# G431.net
KiCad netlist of a schematic drawn in Altium Designer
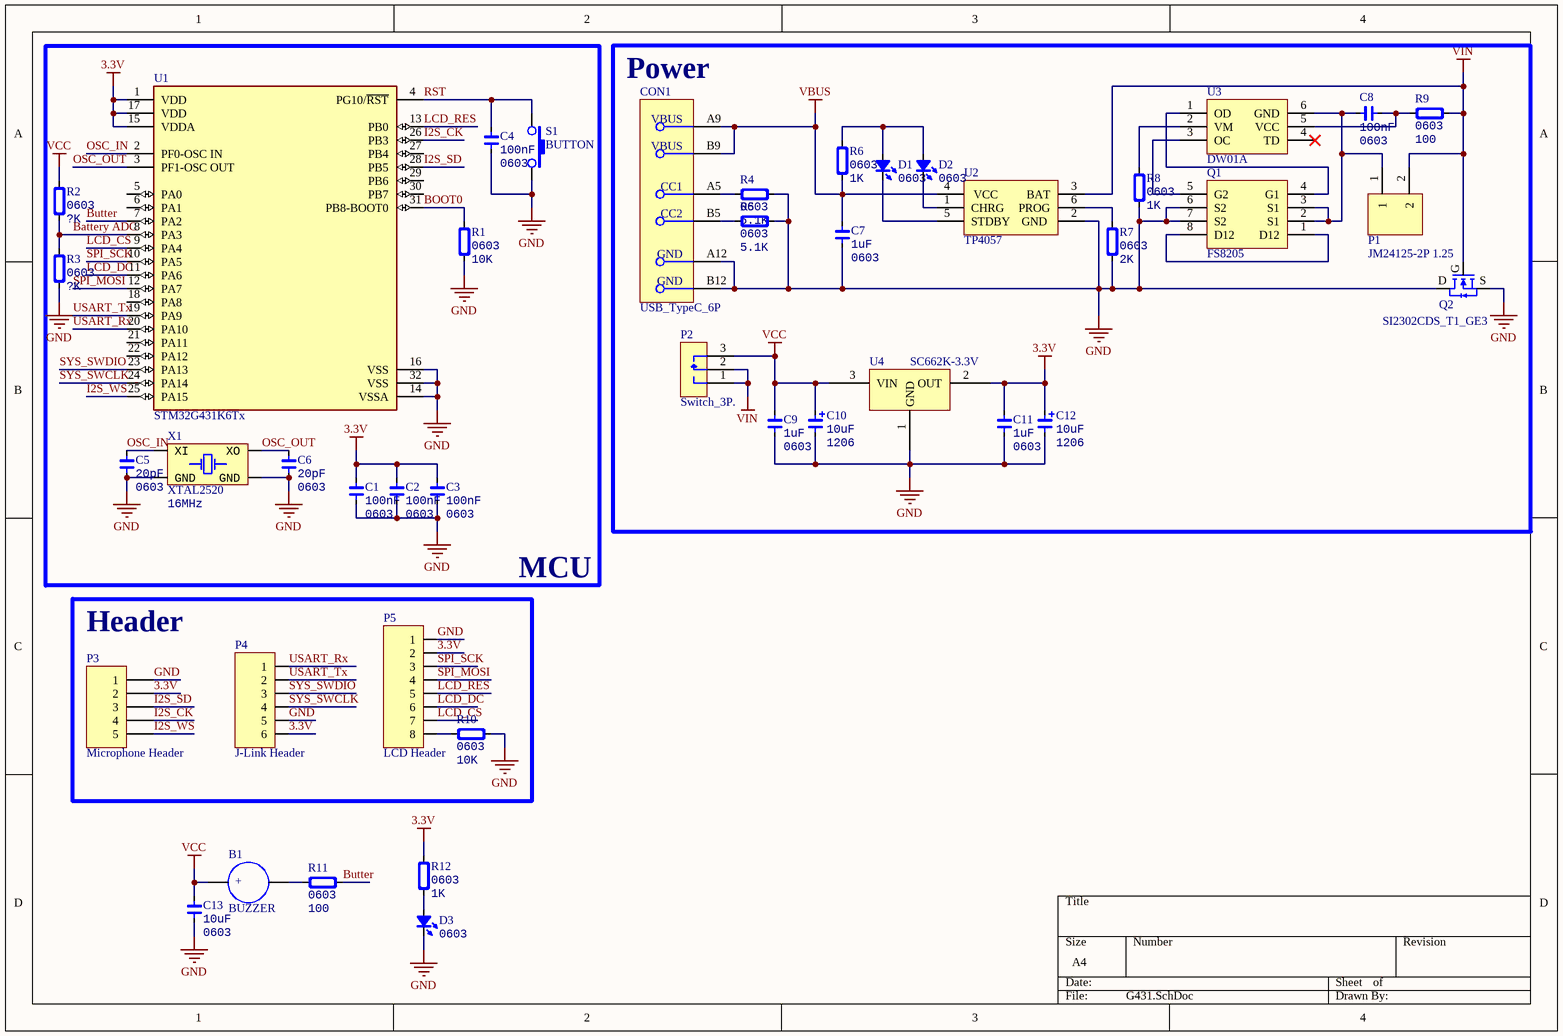
[diagram p0: G431.SchDoc]

(export (version "E")
  (design (tool "Eeschema 10.0.6"))
  (components
    (comp (ref "B1") (value "BUZZER") (footprint "BUZZER - 5020") (libsource (lib "Library") (part "BUZZER")))
    (comp (ref "C1")
      (value "100nF")
      (footprint "CAP_0603")
      (description "Capacitor")
      (fields (field (name "TYPE") "0603") (field (name "Comment") "C0603"))
      (libsource (lib "Library") (part "Cap_0603"))
    )
    (comp (ref "C2")
      (value "100nF")
      (footprint "CAP_0603")
      (description "Capacitor")
      (fields (field (name "TYPE") "0603") (field (name "Comment") "C0603"))
      (libsource (lib "Library") (part "Cap_0603"))
    )
    (comp (ref "C3")
      (value "100nF")
      (footprint "CAP_0603")
      (description "Capacitor")
      (fields (field (name "TYPE") "0603") (field (name "Comment") "C0603"))
      (libsource (lib "Library") (part "Cap_0603"))
    )
    (comp (ref "C4")
      (value "100nF")
      (footprint "CAP_0603")
      (description "Capacitor")
      (fields (field (name "TYPE") "0603") (field (name "Comment") "C0603"))
      (libsource (lib "") (part "Cap_0603_1"))
    )
    (comp (ref "C5")
      (value "20pF")
      (footprint "CAP_0603")
      (description "Capacitor")
      (fields (field (name "TYPE") "0603") (field (name "Comment") "C0603"))
      (libsource (lib "Library") (part "Cap_0603"))
    )
    (comp (ref "C6")
      (value "20pF")
      (footprint "CAP_0603")
      (description "Capacitor")
      (fields (field (name "TYPE") "0603") (field (name "Comment") "C0603"))
      (libsource (lib "Library") (part "Cap_0603"))
    )
    (comp (ref "C7")
      (value "1uF")
      (footprint "CAP_0603")
      (description "Capacitor")
      (fields (field (name "TYPE") "0603") (field (name "Comment") "C0603"))
      (libsource (lib "") (part "Cap_0603_1"))
    )
    (comp (ref "C8")
      (value "100nF")
      (footprint "CAP_0603")
      (description "Capacitor")
      (fields (field (name "TYPE") "0603") (field (name "Comment") "C0603"))
      (libsource (lib "") (part "Cap_0603_2"))
    )
    (comp (ref "C9")
      (value "1uF")
      (footprint "CAP_0603")
      (description "Capacitor")
      (fields (field (name "TYPE") "0603") (field (name "Comment") "C0603"))
      (libsource (lib "") (part "Cap_0603_1"))
    )
    (comp (ref "C10")
      (value "10uF")
      (footprint "CAP_TAN_CASE_A_BK")
      (description "Capacitor Tantalum")
      (fields (field (name "TYPE") "1206") (field (name "Comment") "C1206"))
      (libsource (lib "Library") (part "Cap_Tan_1206"))
    )
    (comp (ref "C11")
      (value "1uF")
      (footprint "CAP_0603")
      (description "Capacitor")
      (fields (field (name "TYPE") "0603") (field (name "Comment") "C0603"))
      (libsource (lib "") (part "Cap_0603_1"))
    )
    (comp (ref "C12")
      (value "10uF")
      (footprint "CAP_TAN_CASE_A_BK")
      (description "Capacitor Tantalum")
      (fields (field (name "TYPE") "1206") (field (name "Comment") "C1206"))
      (libsource (lib "Library") (part "Cap_Tan_1206"))
    )
    (comp (ref "C13")
      (value "10uF")
      (footprint "CAP_0603")
      (description "Capacitor")
      (fields (field (name "TYPE") "0603") (field (name "Comment") "C0603"))
      (libsource (lib "") (part "Cap_0603_1"))
    )
    (comp (ref "CON1")
      (value "USB_TypeC_6P")
      (footprint "USB_TYPEC_6P")
      (libsource (lib "Library") (part "USB_TypeC_6P"))
    )
    (comp (ref "D1")
      (value "D0603")
      (footprint "LED_0603_RED")
      (description "LED")
      (fields (field (name "TYPE") "0603"))
      (libsource (lib "Library") (part "LED_0603"))
    )
    (comp (ref "D2")
      (value "D0603")
      (footprint "LED_0603_RED")
      (description "LED")
      (fields (field (name "TYPE") "0603"))
      (libsource (lib "Library") (part "LED_0603"))
    )
    (comp (ref "D3")
      (value "D0603")
      (footprint "LED_0603_RED")
      (description "LED")
      (fields (field (name "TYPE") "0603"))
      (libsource (lib "Library") (part "LED_0603"))
    )
    (comp (ref "P1")
      (value "JM24125-2P 1.25")
      (footprint "JM24125-2")
      (description "SMT 2P 1.25mm")
      (libsource (lib "Library") (part "JM24125-2P 1.25"))
    )
    (comp (ref "P2")
      (value "Switch_3P.")
      (footprint "SWITCH_3PIN_90")
      (libsource (lib "Library") (part "Switch_3P."))
    )
    (comp (ref "P3")
      (value "Microphone Header")
      (footprint "ICS-43432 Pin")
      (libsource (lib "Library") (part "ICS-43432 Pin"))
    )
    (comp (ref "P4")
      (value "J-Link Header")
      (footprint "Pin Header 1.27mm 1x6")
      (description "Header")
      (libsource (lib "Library") (part "Header 6"))
    )
    (comp (ref "P5")
      (value "LCD Header")
      (footprint "Pin Header 2.54mm 1X8")
      (description "Header")
      (libsource (lib "Library") (part "Header 8"))
    )
    (comp (ref "Q1") (value "FS8205") (footprint "TSSOP8-1") (libsource (lib "Library") (part "FS8205")))
    (comp (ref "Q2")
      (value "SI2302CDS_T1_GE3")
      (footprint "SOT23-3")
      (libsource (lib "Library") (part "SI2302CDS_T1_GE3"))
    )
    (comp (ref "R1")
      (value "10K")
      (footprint "RES_0603")
      (description "Resistor")
      (fields (field (name "TYPE") "0603") (field (name "Comment") "R0603"))
      (libsource (lib "Library") (part "Res_0603"))
    )
    (comp (ref "R2")
      (value "?K")
      (footprint "RES_0603")
      (description "Resistor")
      (fields (field (name "TYPE") "0603") (field (name "Comment") "R0603"))
      (libsource (lib "Library") (part "Res_0603"))
    )
    (comp (ref "R3")
      (value "?K")
      (footprint "RES_0603")
      (description "Resistor")
      (fields (field (name "TYPE") "0603") (field (name "Comment") "R0603"))
      (libsource (lib "Library") (part "Res_0603"))
    )
    (comp (ref "R4")
      (value "5.1K")
      (footprint "RES_0603")
      (description "Resistor")
      (fields (field (name "TYPE") "0603") (field (name "Comment") "R0603"))
      (libsource (lib "Library") (part "Res_0603"))
    )
    (comp (ref "R5")
      (value "5.1K")
      (footprint "RES_0603")
      (description "Resistor")
      (fields (field (name "TYPE") "0603") (field (name "Comment") "R0603"))
      (libsource (lib "Library") (part "Res_0603"))
    )
    (comp (ref "R6")
      (value "1K")
      (footprint "RES_0603")
      (description "Resistor")
      (fields (field (name "TYPE") "0603") (field (name "Comment") "R0603"))
      (libsource (lib "Library") (part "Res_0603"))
    )
    (comp (ref "R7")
      (value "2K")
      (footprint "RES_0603")
      (description "Resistor")
      (fields (field (name "TYPE") "0603") (field (name "Comment") "R0603"))
      (libsource (lib "Library") (part "Res_0603"))
    )
    (comp (ref "R8")
      (value "1K")
      (footprint "RES_0603")
      (description "Resistor")
      (fields (field (name "TYPE") "0603") (field (name "Comment") "R0603"))
      (libsource (lib "Library") (part "Res_0603"))
    )
    (comp (ref "R9")
      (value "100")
      (footprint "RES_0603")
      (description "Resistor")
      (fields (field (name "TYPE") "0603") (field (name "Comment") "R0603"))
      (libsource (lib "Library") (part "Res_0603"))
    )
    (comp (ref "R10")
      (value "10K")
      (footprint "RES_0603")
      (description "Resistor")
      (fields (field (name "TYPE") "0603") (field (name "Comment") "R0603"))
      (libsource (lib "Library") (part "Res_0603"))
    )
    (comp (ref "R11")
      (value "100")
      (footprint "RES_0603")
      (description "Resistor")
      (fields (field (name "TYPE") "0603") (field (name "Comment") "R0603"))
      (libsource (lib "Library") (part "Res_0603"))
    )
    (comp (ref "R12")
      (value "1K")
      (footprint "RES_0603")
      (description "Resistor")
      (fields (field (name "TYPE") "0603") (field (name "Comment") "R0603"))
      (libsource (lib "Library") (part "Res_0603"))
    )
    (comp (ref "S1") (value "BUTTON") (footprint "BUTTON - SMD") (libsource (lib "Library") (part "BUTTON")))
    (comp (ref "U1")
      (value "STM32G431K6Tx")
      (footprint "LQFP_P0.8_32")
      (description "MCU Mainstream Arm Cortex-M4 MCU 170 MHz 32 Kbytes of Flash Math Accel, Medium Analo")
      (libsource (lib "Library") (part "STM32G431K6Tx"))
    )
    (comp (ref "U2")
      (value "TP4057")
      (footprint "SOT23-6")
      (description "Battery Charging IC 500 mA")
      (libsource (lib "Library") (part "TP4057"))
    )
    (comp (ref "U3") (value "DW01A") (footprint "SOT23-6-1") (libsource (lib "Library") (part "DW01A")))
    (comp (ref "U4")
      (value "SC662K-3.3V")
      (footprint "SOT23-3")
      (description "LDO 300mA")
      (libsource (lib "Library") (part "SC662K-3.3V"))
    )
    (comp (ref "X1")
      (value "XTAL2520")
      (footprint "XT_2520_4")
      (description "Crystal Oscillator")
      (fields (field (name "ALTIUM_VALUE") "16MHz"))
      (libsource (lib "Library") (part "XTAL_2520_4P"))
    )
  )
  (nets
    (net (code "1") (name "/BOOT0") (class "Default")
      (node (ref "R1") (pin "1") (pinfunction "1_1") (pintype "passive"))
      (node (ref "U1") (pin "31") (pinfunction "PB8-BOOT0_31") (pintype "bidirectional"))
    )
    (net (code "2") (name "/Battery ADC") (class "Default")
      (node (ref "R2") (pin "1") (pinfunction "1_1") (pintype "passive"))
      (node (ref "R3") (pin "2") (pinfunction "2_2") (pintype "passive"))
      (node (ref "U1") (pin "8") (pinfunction "PA3_8") (pintype "bidirectional"))
    )
    (net (code "3") (name "/Butter") (class "Default")
      (node (ref "R11") (pin "2") (pinfunction "2_2") (pintype "passive"))
      (node (ref "U1") (pin "7") (pinfunction "PA2_7") (pintype "bidirectional"))
    )
    (net (code "4") (name "/I2S_CK") (class "Default")
      (node (ref "P3") (pin "4") (pinfunction "4_4") (pintype "passive"))
      (node (ref "U1") (pin "26") (pinfunction "PB3_26") (pintype "bidirectional"))
    )
    (net (code "5") (name "/I2S_SD") (class "Default")
      (node (ref "P3") (pin "3") (pinfunction "3_3") (pintype "passive"))
      (node (ref "U1") (pin "28") (pinfunction "PB5_28") (pintype "bidirectional"))
    )
    (net (code "6") (name "/I2S_WS") (class "Default")
      (node (ref "P3") (pin "5") (pinfunction "5_5") (pintype "passive"))
      (node (ref "U1") (pin "25") (pinfunction "PA15_25") (pintype "bidirectional"))
    )
    (net (code "7") (name "/LCD_CS") (class "Default")
      (node (ref "P5") (pin "7") (pinfunction "7_7") (pintype "passive"))
      (node (ref "U1") (pin "9") (pinfunction "PA4_9") (pintype "bidirectional"))
    )
    (net (code "8") (name "/LCD_DC") (class "Default")
      (node (ref "P5") (pin "6") (pinfunction "6_6") (pintype "passive"))
      (node (ref "U1") (pin "11") (pinfunction "PA6_11") (pintype "bidirectional"))
    )
    (net (code "9") (name "/LCD_RES") (class "Default")
      (node (ref "P5") (pin "5") (pinfunction "5_5") (pintype "passive"))
      (node (ref "U1") (pin "13") (pinfunction "PB0_13") (pintype "bidirectional"))
    )
    (net (code "10") (name "/OSC_IN") (class "Default")
      (node (ref "C5") (pin "2") (pinfunction "2_2") (pintype "passive"))
      (node (ref "U1") (pin "2") (pinfunction "PF0-OSC_IN_2") (pintype "passive"))
      (node (ref "X1") (pin "1") (pinfunction "XI_1") (pintype "passive"))
    )
    (net (code "11") (name "/OSC_OUT") (class "Default")
      (node (ref "C6") (pin "2") (pinfunction "2_2") (pintype "passive"))
      (node (ref "U1") (pin "3") (pinfunction "PF1-OSC_OUT_3") (pintype "passive"))
      (node (ref "X1") (pin "3") (pinfunction "XO_3") (pintype "passive"))
    )
    (net (code "12") (name "/RST") (class "Default")
      (node (ref "C4") (pin "1") (pinfunction "1_1") (pintype "passive"))
      (node (ref "S1") (pin "1") (pinfunction "1_1") (pintype "passive"))
      (node (ref "U1") (pin "4") (pinfunction "PG10/~{RST}_4") (pintype "passive"))
    )
    (net (code "13") (name "/SPI_MOSI") (class "Default")
      (node (ref "P5") (pin "4") (pinfunction "4_4") (pintype "passive"))
      (node (ref "U1") (pin "12") (pinfunction "PA7_12") (pintype "bidirectional"))
    )
    (net (code "14") (name "/SPI_SCK") (class "Default")
      (node (ref "P5") (pin "3") (pinfunction "3_3") (pintype "passive"))
      (node (ref "U1") (pin "10") (pinfunction "PA5_10") (pintype "bidirectional"))
    )
    (net (code "15") (name "/SYS_SWCLK") (class "Default")
      (node (ref "P4") (pin "4") (pinfunction "4_4") (pintype "passive"))
      (node (ref "U1") (pin "24") (pinfunction "PA14_24") (pintype "bidirectional"))
    )
    (net (code "16") (name "/SYS_SWDIO") (class "Default")
      (node (ref "P4") (pin "3") (pinfunction "3_3") (pintype "passive"))
      (node (ref "U1") (pin "23") (pinfunction "PA13_23") (pintype "bidirectional"))
    )
    (net (code "17") (name "/USART_Rx") (class "Default")
      (node (ref "P4") (pin "1") (pinfunction "1_1") (pintype "passive"))
      (node (ref "U1") (pin "20") (pinfunction "PA10_20") (pintype "bidirectional"))
    )
    (net (code "18") (name "/USART_Tx") (class "Default")
      (node (ref "P4") (pin "2") (pinfunction "2_2") (pintype "passive"))
      (node (ref "U1") (pin "19") (pinfunction "PA9_19") (pintype "bidirectional"))
    )
    (net (code "19") (name "3.3V") (class "Default")
      (node (ref "C1") (pin "2") (pinfunction "2_2") (pintype "passive"))
      (node (ref "C11") (pin "1") (pinfunction "1_1") (pintype "passive"))
      (node (ref "C12") (pin "1") (pinfunction "1_1") (pintype "passive"))
      (node (ref "C2") (pin "2") (pinfunction "2_2") (pintype "passive"))
      (node (ref "C3") (pin "2") (pinfunction "2_2") (pintype "passive"))
      (node (ref "P3") (pin "2") (pinfunction "2_2") (pintype "passive"))
      (node (ref "P4") (pin "6") (pinfunction "6_6") (pintype "passive"))
      (node (ref "P5") (pin "2") (pinfunction "2_2") (pintype "passive"))
      (node (ref "R12") (pin "1") (pinfunction "1_1") (pintype "passive"))
      (node (ref "U1") (pin "1") (pinfunction "VDD_1") (pintype "power_in"))
      (node (ref "U1") (pin "15") (pinfunction "VDDA_15") (pintype "power_in"))
      (node (ref "U1") (pin "17") (pinfunction "VDD_17") (pintype "power_in"))
      (node (ref "U4") (pin "2") (pinfunction "OUT_2") (pintype "passive"))
    )
    (net (code "20") (name "GND") (class "Default")
      (node (ref "C1") (pin "1") (pinfunction "1_1") (pintype "passive"))
      (node (ref "C10") (pin "2") (pinfunction "2_2") (pintype "passive"))
      (node (ref "C11") (pin "2") (pinfunction "2_2") (pintype "passive"))
      (node (ref "C12") (pin "2") (pinfunction "2_2") (pintype "passive"))
      (node (ref "C13") (pin "2") (pinfunction "2_2") (pintype "passive"))
      (node (ref "C2") (pin "1") (pinfunction "1_1") (pintype "passive"))
      (node (ref "C3") (pin "1") (pinfunction "1_1") (pintype "passive"))
      (node (ref "C4") (pin "2") (pinfunction "2_2") (pintype "passive"))
      (node (ref "C5") (pin "1") (pinfunction "1_1") (pintype "passive"))
      (node (ref "C6") (pin "1") (pinfunction "1_1") (pintype "passive"))
      (node (ref "C7") (pin "2") (pinfunction "2_2") (pintype "passive"))
      (node (ref "C9") (pin "2") (pinfunction "2_2") (pintype "passive"))
      (node (ref "CON1") (pin "A12") (pinfunction "GND_A12") (pintype "passive"))
      (node (ref "CON1") (pin "B12") (pinfunction "GND_B12") (pintype "passive"))
      (node (ref "D3") (pin "2") (pinfunction "K_2") (pintype "passive"))
      (node (ref "P3") (pin "1") (pinfunction "1_1") (pintype "passive"))
      (node (ref "P4") (pin "5") (pinfunction "5_5") (pintype "passive"))
      (node (ref "P5") (pin "1") (pinfunction "1_1") (pintype "passive"))
      (node (ref "Q1") (pin "6") (pinfunction "S2_6") (pintype "passive"))
      (node (ref "Q1") (pin "7") (pinfunction "S2_7") (pintype "passive"))
      (node (ref "Q2") (pin "2") (pinfunction "S_2") (pintype "passive"))
      (node (ref "Q2") (pin "3") (pinfunction "D_3") (pintype "passive"))
      (node (ref "R1") (pin "2") (pinfunction "2_2") (pintype "passive"))
      (node (ref "R10") (pin "2") (pinfunction "2_2") (pintype "passive"))
      (node (ref "R3") (pin "1") (pinfunction "1_1") (pintype "passive"))
      (node (ref "R4") (pin "1") (pinfunction "1_1") (pintype "passive"))
      (node (ref "R5") (pin "1") (pinfunction "1_1") (pintype "passive"))
      (node (ref "R7") (pin "2") (pinfunction "2_2") (pintype "passive"))
      (node (ref "R8") (pin "2") (pinfunction "2_2") (pintype "passive"))
      (node (ref "S1") (pin "2") (pinfunction "2_2") (pintype "passive"))
      (node (ref "U1") (pin "14") (pinfunction "VSSA_14") (pintype "power_in"))
      (node (ref "U1") (pin "16") (pinfunction "VSS_16") (pintype "power_in"))
      (node (ref "U1") (pin "32") (pinfunction "VSS_32") (pintype "power_in"))
      (node (ref "U2") (pin "2") (pinfunction "GND_2") (pintype "passive"))
      (node (ref "U4") (pin "1") (pinfunction "GND_1") (pintype "passive"))
      (node (ref "X1") (pin "2") (pinfunction "GND_2") (pintype "passive"))
      (node (ref "X1") (pin "4") (pinfunction "GND_4") (pintype "passive"))
    )
    (net (code "21") (name "Net-(B1-Pad2)") (class "Default")
      (node (ref "B1") (pin "2") (pinfunction "2_2") (pintype "passive"))
      (node (ref "R11") (pin "1") (pinfunction "1_1") (pintype "passive"))
    )
    (net (code "22") (name "Net-(CON1-CC1)") (class "Default")
      (node (ref "CON1") (pin "A5") (pinfunction "CC1_A5") (pintype "passive"))
      (node (ref "R4") (pin "2") (pinfunction "2_2") (pintype "passive"))
    )
    (net (code "23") (name "Net-(CON1-CC2)") (class "Default")
      (node (ref "CON1") (pin "B5") (pinfunction "CC2_B5") (pintype "passive"))
      (node (ref "R5") (pin "2") (pinfunction "2_2") (pintype "passive"))
    )
    (net (code "24") (name "Net-(D1-A)") (class "Default")
      (node (ref "D1") (pin "1") (pinfunction "A_1") (pintype "passive"))
      (node (ref "D2") (pin "1") (pinfunction "A_1") (pintype "passive"))
      (node (ref "R6") (pin "1") (pinfunction "1_1") (pintype "passive"))
    )
    (net (code "25") (name "Net-(D1-K)") (class "Default")
      (node (ref "D1") (pin "2") (pinfunction "K_2") (pintype "passive"))
      (node (ref "U2") (pin "5") (pinfunction "STDBY_5") (pintype "passive"))
    )
    (net (code "26") (name "Net-(D2-K)") (class "Default")
      (node (ref "D2") (pin "2") (pinfunction "K_2") (pintype "passive"))
      (node (ref "U2") (pin "1") (pinfunction "CHRG_1") (pintype "passive"))
    )
    (net (code "27") (name "Net-(D3-A)") (class "Default")
      (node (ref "D3") (pin "1") (pinfunction "A_1") (pintype "passive"))
      (node (ref "R12") (pin "2") (pinfunction "2_2") (pintype "passive"))
    )
    (net (code "28") (name "Net-(P5-Pad8)") (class "Default")
      (node (ref "P5") (pin "8") (pinfunction "8_8") (pintype "passive"))
      (node (ref "R10") (pin "1") (pinfunction "1_1") (pintype "passive"))
    )
    (net (code "29") (name "Net-(Q1-D12-Pad1)") (class "Default")
      (node (ref "Q1") (pin "1") (pinfunction "D12_1") (pintype "passive"))
      (node (ref "Q1") (pin "8") (pinfunction "D12_8") (pintype "passive"))
    )
    (net (code "30") (name "Net-(Q1-G1)") (class "Default")
      (node (ref "Q1") (pin "4") (pinfunction "G1_4") (pintype "passive"))
      (node (ref "U3") (pin "1") (pinfunction "OD_1") (pintype "passive"))
    )
    (net (code "31") (name "Net-(Q1-G2)") (class "Default")
      (node (ref "Q1") (pin "5") (pinfunction "G2_5") (pintype "passive"))
      (node (ref "U3") (pin "3") (pinfunction "OC_3") (pintype "passive"))
    )
    (net (code "32") (name "Net-(U2-PROG)") (class "Default")
      (node (ref "R7") (pin "1") (pinfunction "1_1") (pintype "passive"))
      (node (ref "U2") (pin "6") (pinfunction "PROG_6") (pintype "passive"))
    )
    (net (code "33") (name "Net-(U3-GND)") (class "Default")
      (node (ref "C8") (pin "1") (pinfunction "1_1") (pintype "passive"))
      (node (ref "P1") (pin "1") (pinfunction "1_1") (pintype "passive"))
      (node (ref "Q1") (pin "2") (pinfunction "S1_2") (pintype "passive"))
      (node (ref "Q1") (pin "3") (pinfunction "S1_3") (pintype "passive"))
      (node (ref "U3") (pin "6") (pinfunction "GND_6") (pintype "passive"))
    )
    (net (code "34") (name "Net-(U3-VCC)") (class "Default")
      (node (ref "C8") (pin "2") (pinfunction "2_2") (pintype "passive"))
      (node (ref "R9") (pin "1") (pinfunction "1_1") (pintype "passive"))
      (node (ref "U3") (pin "5") (pinfunction "VCC_5") (pintype "passive"))
    )
    (net (code "35") (name "Net-(U3-VM)") (class "Default")
      (node (ref "R8") (pin "1") (pinfunction "1_1") (pintype "passive"))
      (node (ref "U3") (pin "2") (pinfunction "VM_2") (pintype "passive"))
    )
    (net (code "36") (name "VBUS") (class "Default")
      (node (ref "C7") (pin "1") (pinfunction "1_1") (pintype "passive"))
      (node (ref "CON1") (pin "A9") (pinfunction "VBUS_A9") (pintype "passive"))
      (node (ref "CON1") (pin "B9") (pinfunction "VBUS_B9") (pintype "passive"))
      (node (ref "R6") (pin "2") (pinfunction "2_2") (pintype "passive"))
      (node (ref "U2") (pin "4") (pinfunction "VCC_4") (pintype "passive"))
    )
    (net (code "37") (name "VCC") (class "Default")
      (node (ref "B1") (pin "1") (pinfunction "1_1") (pintype "passive"))
      (node (ref "C10") (pin "1") (pinfunction "1_1") (pintype "passive"))
      (node (ref "C13") (pin "1") (pinfunction "1_1") (pintype "passive"))
      (node (ref "C9") (pin "1") (pinfunction "1_1") (pintype "passive"))
      (node (ref "P2") (pin "3") (pinfunction "3_3") (pintype "passive"))
      (node (ref "R2") (pin "2") (pinfunction "2_2") (pintype "passive"))
      (node (ref "U4") (pin "3") (pinfunction "VIN_3") (pintype "passive"))
    )
    (net (code "38") (name "VIN") (class "Default")
      (node (ref "P1") (pin "2") (pinfunction "2_2") (pintype "passive"))
      (node (ref "P2") (pin "1") (pinfunction "1_1") (pintype "passive"))
      (node (ref "P2") (pin "2") (pinfunction "2_2") (pintype "passive"))
      (node (ref "Q2") (pin "1") (pinfunction "G_1") (pintype "passive"))
      (node (ref "R9") (pin "2") (pinfunction "2_2") (pintype "passive"))
      (node (ref "U2") (pin "3") (pinfunction "BAT_3") (pintype "passive"))
    )
    (net (code "39") (name "unconnected-(U1-PA0-Pad5)") (class "Default")
      (node (ref "U1") (pin "5") (pinfunction "PA0_5") (pintype "bidirectional"))
    )
    (net (code "40") (name "unconnected-(U1-PA1-Pad6)") (class "Default")
      (node (ref "U1") (pin "6") (pinfunction "PA1_6") (pintype "bidirectional"))
    )
    (net (code "41") (name "unconnected-(U1-PA8-Pad18)") (class "Default")
      (node (ref "U1") (pin "18") (pinfunction "PA8_18") (pintype "bidirectional"))
    )
    (net (code "42") (name "unconnected-(U1-PA11-Pad21)") (class "Default")
      (node (ref "U1") (pin "21") (pinfunction "PA11_21") (pintype "bidirectional"))
    )
    (net (code "43") (name "unconnected-(U1-PA12-Pad22)") (class "Default")
      (node (ref "U1") (pin "22") (pinfunction "PA12_22") (pintype "bidirectional"))
    )
    (net (code "44") (name "unconnected-(U1-PB4-Pad27)") (class "Default")
      (node (ref "U1") (pin "27") (pinfunction "PB4_27") (pintype "bidirectional"))
    )
    (net (code "45") (name "unconnected-(U1-PB6-Pad29)") (class "Default")
      (node (ref "U1") (pin "29") (pinfunction "PB6_29") (pintype "bidirectional"))
    )
    (net (code "46") (name "unconnected-(U1-PB7-Pad30)") (class "Default")
      (node (ref "U1") (pin "30") (pinfunction "PB7_30") (pintype "bidirectional"))
    )
    (net (code "47") (name "unconnected-(U3-TD-Pad4)") (class "Default")
      (node (ref "U3") (pin "4") (pinfunction "TD_4") (pintype "passive+no_connect"))
    )
  )
)
